# kludge.net
KiCad netlist of a schematic drawn in EAGLE
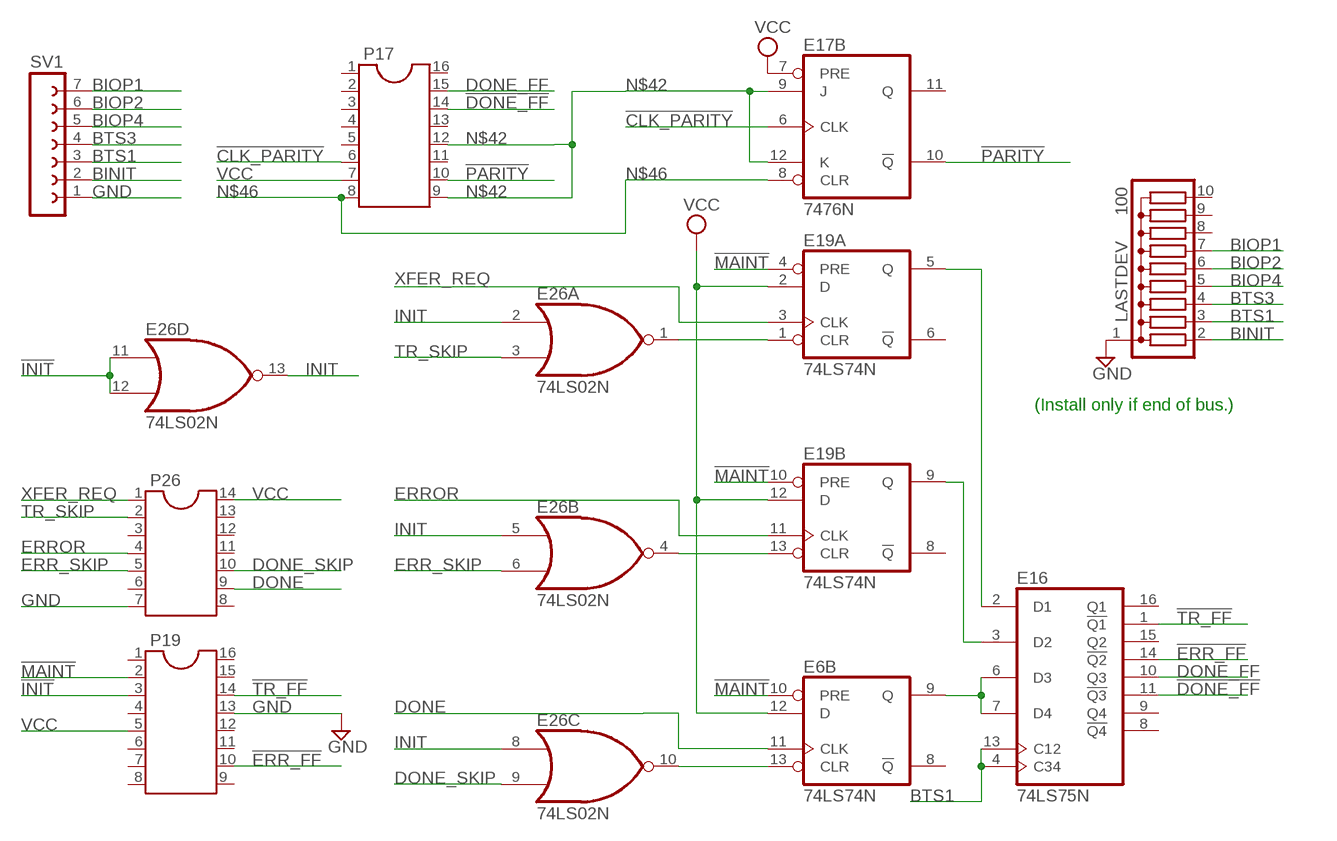
[diagram p0: schematic, sheet 1]

(export (version "E")
  (design (tool "Eeschema 10.0.6"))
  (components
    (comp (ref "E6")
      (value "74LS74N")
      (footprint "eagle-import:DIL14")
      (libsource (lib "eagle-import") (part "7474NLS"))
    )
    (comp (ref "E16")
      (value "74LS75N")
      (footprint "eagle-import:DIL16")
      (libsource (lib "eagle-import") (part "7475NLS"))
    )
    (comp (ref "E17")
      (value "7476N")
      (footprint "eagle-import:DIL16")
      (libsource (lib "eagle-import") (part "7476N"))
    )
    (comp (ref "E19")
      (value "74LS74N")
      (footprint "eagle-import:DIL14")
      (libsource (lib "eagle-import") (part "7474NLS"))
    )
    (comp (ref "E26")
      (value "74LS02N")
      (footprint "eagle-import:DIL14")
      (libsource (lib "eagle-import") (part "7402NLS"))
    )
    (comp (ref "LASTDEV")
      (value "100")
      (footprint "eagle-import:SIL10")
      (libsource (lib "eagle-import") (part "G09R"))
    )
    (comp (ref "P17")
      (value "DIL16")
      (footprint "eagle-import:DIL16")
      (libsource (lib "eagle-import") (part "DIL16"))
    )
    (comp (ref "P19")
      (value "DIL16")
      (footprint "eagle-import:DIL16")
      (libsource (lib "eagle-import") (part "DIL16"))
    )
    (comp (ref "P26")
      (value "DIL14")
      (footprint "eagle-import:DIL14")
      (libsource (lib "eagle-import") (part "DIL14"))
    )
    (comp (ref "SV1")
      (value "FE07-1")
      (footprint "eagle-import:FE07")
      (libsource (lib "eagle-import") (part "FE07-1"))
    )
  )
  (nets
    (net (code "1") (name "/BINIT") (class "Default")
      (node (ref "LASTDEV") (pin "2") (pinfunction "2_2") (pintype "passive"))
      (node (ref "SV1") (pin "2") (pinfunction "2_2") (pintype "passive"))
    )
    (net (code "2") (name "/BIOP1") (class "Default")
      (node (ref "LASTDEV") (pin "7") (pinfunction "7_7") (pintype "passive"))
      (node (ref "SV1") (pin "7") (pinfunction "7_7") (pintype "passive"))
    )
    (net (code "3") (name "/BIOP2") (class "Default")
      (node (ref "LASTDEV") (pin "6") (pinfunction "6_6") (pintype "passive"))
      (node (ref "SV1") (pin "6") (pinfunction "6_6") (pintype "passive"))
    )
    (net (code "4") (name "/BIOP4") (class "Default")
      (node (ref "LASTDEV") (pin "5") (pinfunction "5_5") (pintype "passive"))
      (node (ref "SV1") (pin "5") (pinfunction "5_5") (pintype "passive"))
    )
    (net (code "5") (name "/BTS1") (class "Default")
      (node (ref "E16") (pin "13") (pinfunction "C12_13") (pintype "input"))
      (node (ref "E16") (pin "4") (pinfunction "C34_4") (pintype "input"))
      (node (ref "LASTDEV") (pin "3") (pinfunction "3_3") (pintype "passive"))
      (node (ref "SV1") (pin "3") (pinfunction "3_3") (pintype "passive"))
    )
    (net (code "6") (name "/BTS3") (class "Default")
      (node (ref "LASTDEV") (pin "4") (pinfunction "4_4") (pintype "passive"))
      (node (ref "SV1") (pin "4") (pinfunction "4_4") (pintype "passive"))
    )
    (net (code "7") (name "/DONE") (class "Default")
      (node (ref "E6") (pin "11") (pinfunction "CLK_11") (pintype "input"))
      (node (ref "P26") (pin "9") (pinfunction "9_9") (pintype "passive"))
    )
    (net (code "8") (name "/DONE_FF") (class "Default")
      (node (ref "E16") (pin "10") (pinfunction "Q3_10") (pintype "output"))
      (node (ref "P17") (pin "15") (pinfunction "15_15") (pintype "passive"))
    )
    (net (code "9") (name "/DONE_SKIP") (class "Default")
      (node (ref "E26") (pin "9") (pinfunction "I1_9") (pintype "input"))
      (node (ref "P26") (pin "10") (pinfunction "10_10") (pintype "passive"))
    )
    (net (code "10") (name "/ERROR") (class "Default")
      (node (ref "E19") (pin "11") (pinfunction "CLK_11") (pintype "input"))
      (node (ref "P26") (pin "4") (pinfunction "4_4") (pintype "passive"))
    )
    (net (code "11") (name "/ERR_SKIP") (class "Default")
      (node (ref "E26") (pin "6") (pinfunction "I1_6") (pintype "input"))
      (node (ref "P26") (pin "5") (pinfunction "5_5") (pintype "passive"))
    )
    (net (code "12") (name "/INIT") (class "Default")
      (node (ref "E26") (pin "13") (pinfunction "O_13") (pintype "output"))
      (node (ref "E26") (pin "2") (pinfunction "I0_2") (pintype "input"))
      (node (ref "E26") (pin "5") (pinfunction "I0_5") (pintype "input"))
      (node (ref "E26") (pin "8") (pinfunction "I0_8") (pintype "input"))
    )
    (net (code "13") (name "/N$42") (class "Default")
      (node (ref "E17") (pin "12") (pinfunction "K_12") (pintype "input"))
      (node (ref "E17") (pin "9") (pinfunction "J_9") (pintype "input"))
      (node (ref "P17") (pin "12") (pinfunction "12_12") (pintype "passive"))
      (node (ref "P17") (pin "9") (pinfunction "9_9") (pintype "passive"))
    )
    (net (code "14") (name "/N$46") (class "Default")
      (node (ref "E17") (pin "8") (pinfunction "CLR_8") (pintype "input"))
      (node (ref "P17") (pin "8") (pinfunction "8_8") (pintype "passive"))
    )
    (net (code "15") (name "/TR_SKIP") (class "Default")
      (node (ref "E26") (pin "3") (pinfunction "I1_3") (pintype "input"))
      (node (ref "P26") (pin "2") (pinfunction "2_2") (pintype "passive"))
    )
    (net (code "16") (name "/XFER_REQ") (class "Default")
      (node (ref "E19") (pin "3") (pinfunction "CLK_3") (pintype "input"))
      (node (ref "P26") (pin "1") (pinfunction "1_1") (pintype "passive"))
    )
    (net (code "17") (name "/~{CLK_PARITY}") (class "Default")
      (node (ref "E17") (pin "6") (pinfunction "CLK_6") (pintype "input"))
      (node (ref "P17") (pin "6") (pinfunction "6_6") (pintype "passive"))
    )
    (net (code "18") (name "/~{DONE_FF}") (class "Default")
      (node (ref "E16") (pin "11") (pinfunction "~{Q3}_11") (pintype "output"))
      (node (ref "P17") (pin "14") (pinfunction "14_14") (pintype "passive"))
    )
    (net (code "19") (name "/~{ERR_FF}") (class "Default")
      (node (ref "E16") (pin "14") (pinfunction "~{Q2}_14") (pintype "output"))
      (node (ref "P19") (pin "10") (pinfunction "10_10") (pintype "passive"))
    )
    (net (code "20") (name "/~{INIT}") (class "Default")
      (node (ref "E26") (pin "11") (pinfunction "I0_11") (pintype "input"))
      (node (ref "E26") (pin "12") (pinfunction "I1_12") (pintype "input"))
      (node (ref "P19") (pin "3") (pinfunction "3_3") (pintype "passive"))
    )
    (net (code "21") (name "/~{MAINT}") (class "Default")
      (node (ref "E19") (pin "10") (pinfunction "PRE_10") (pintype "input"))
      (node (ref "E19") (pin "4") (pinfunction "PRE_4") (pintype "input"))
      (node (ref "E6") (pin "10") (pinfunction "PRE_10") (pintype "input"))
      (node (ref "P19") (pin "2") (pinfunction "2_2") (pintype "passive"))
    )
    (net (code "22") (name "/~{PARITY}") (class "Default")
      (node (ref "E17") (pin "10") (pinfunction "~{Q}_10") (pintype "output"))
      (node (ref "P17") (pin "10") (pinfunction "10_10") (pintype "passive"))
    )
    (net (code "23") (name "/~{TR_FF}") (class "Default")
      (node (ref "E16") (pin "1") (pinfunction "~{Q1}_1") (pintype "output"))
      (node (ref "P19") (pin "14") (pinfunction "14_14") (pintype "passive"))
    )
    (net (code "24") (name "GND") (class "Default")
      (node (ref "LASTDEV") (pin "1") (pinfunction "1_1") (pintype "passive"))
      (node (ref "P19") (pin "13") (pinfunction "13_13") (pintype "passive"))
      (node (ref "P26") (pin "7") (pinfunction "7_7") (pintype "passive"))
      (node (ref "SV1") (pin "1") (pinfunction "1_1") (pintype "passive"))
    )
    (net (code "25") (name "Net-(E16A-D1)") (class "Default")
      (node (ref "E16") (pin "2") (pinfunction "D1_2") (pintype "input"))
      (node (ref "E19") (pin "5") (pinfunction "Q_5") (pintype "output"))
    )
    (net (code "26") (name "Net-(E16A-D2)") (class "Default")
      (node (ref "E16") (pin "3") (pinfunction "D2_3") (pintype "input"))
      (node (ref "E19") (pin "9") (pinfunction "Q_9") (pintype "output"))
    )
    (net (code "27") (name "Net-(E16A-D3)") (class "Default")
      (node (ref "E16") (pin "6") (pinfunction "D3_6") (pintype "input"))
      (node (ref "E16") (pin "7") (pinfunction "D4_7") (pintype "input"))
      (node (ref "E6") (pin "9") (pinfunction "Q_9") (pintype "output"))
    )
    (net (code "28") (name "Net-(E19A-CLR)") (class "Default")
      (node (ref "E19") (pin "1") (pinfunction "CLR_1") (pintype "input"))
      (node (ref "E26") (pin "1") (pinfunction "O_1") (pintype "output"))
    )
    (net (code "29") (name "Net-(E19B-CLR)") (class "Default")
      (node (ref "E19") (pin "13") (pinfunction "CLR_13") (pintype "input"))
      (node (ref "E26") (pin "4") (pinfunction "O_4") (pintype "output"))
    )
    (net (code "30") (name "Net-(E26C-O)") (class "Default")
      (node (ref "E26") (pin "10") (pinfunction "O_10") (pintype "output"))
      (node (ref "E6") (pin "13") (pinfunction "CLR_13") (pintype "input"))
    )
    (net (code "31") (name "VCC") (class "Default")
      (node (ref "E17") (pin "7") (pinfunction "PRE_7") (pintype "input"))
      (node (ref "E19") (pin "12") (pinfunction "D_12") (pintype "input"))
      (node (ref "E19") (pin "2") (pinfunction "D_2") (pintype "input"))
      (node (ref "E6") (pin "12") (pinfunction "D_12") (pintype "input"))
      (node (ref "P17") (pin "7") (pinfunction "7_7") (pintype "passive"))
      (node (ref "P19") (pin "5") (pinfunction "5_5") (pintype "passive"))
      (node (ref "P26") (pin "14") (pinfunction "14_14") (pintype "passive"))
    )
    (net (code "32") (name "unconnected-(E6B-~{Q}-Pad8)") (class "Default")
      (node (ref "E6") (pin "8") (pinfunction "~{Q}_8") (pintype "output"))
    )
    (net (code "33") (name "unconnected-(E16A-Q1-Pad16)") (class "Default")
      (node (ref "E16") (pin "16") (pinfunction "Q1_16") (pintype "output"))
    )
    (net (code "34") (name "unconnected-(E16A-Q2-Pad15)") (class "Default")
      (node (ref "E16") (pin "15") (pinfunction "Q2_15") (pintype "output"))
    )
    (net (code "35") (name "unconnected-(E16A-Q4-Pad9)") (class "Default")
      (node (ref "E16") (pin "9") (pinfunction "Q4_9") (pintype "output"))
    )
    (net (code "36") (name "unconnected-(E16A-~{Q4}-Pad8)") (class "Default")
      (node (ref "E16") (pin "8") (pinfunction "~{Q4}_8") (pintype "output"))
    )
    (net (code "37") (name "unconnected-(E17B-Q-Pad11)") (class "Default")
      (node (ref "E17") (pin "11") (pinfunction "Q_11") (pintype "output"))
    )
    (net (code "38") (name "unconnected-(E19A-~{Q}-Pad6)") (class "Default")
      (node (ref "E19") (pin "6") (pinfunction "~{Q}_6") (pintype "output"))
    )
    (net (code "39") (name "unconnected-(E19B-~{Q}-Pad8)") (class "Default")
      (node (ref "E19") (pin "8") (pinfunction "~{Q}_8") (pintype "output"))
    )
    (net (code "40") (name "unconnected-(LASTDEV-Pad8)") (class "Default")
      (node (ref "LASTDEV") (pin "8") (pinfunction "8_8") (pintype "passive"))
    )
    (net (code "41") (name "unconnected-(LASTDEV-Pad9)") (class "Default")
      (node (ref "LASTDEV") (pin "9") (pinfunction "9_9") (pintype "passive"))
    )
    (net (code "42") (name "unconnected-(LASTDEV-Pad10)") (class "Default")
      (node (ref "LASTDEV") (pin "10") (pinfunction "10_10") (pintype "passive"))
    )
    (net (code "43") (name "unconnected-(P17-Pad1)") (class "Default")
      (node (ref "P17") (pin "1") (pinfunction "1_1") (pintype "passive"))
    )
    (net (code "44") (name "unconnected-(P17-Pad2)") (class "Default")
      (node (ref "P17") (pin "2") (pinfunction "2_2") (pintype "passive"))
    )
    (net (code "45") (name "unconnected-(P17-Pad3)") (class "Default")
      (node (ref "P17") (pin "3") (pinfunction "3_3") (pintype "passive"))
    )
    (net (code "46") (name "unconnected-(P17-Pad4)") (class "Default")
      (node (ref "P17") (pin "4") (pinfunction "4_4") (pintype "passive"))
    )
    (net (code "47") (name "unconnected-(P17-Pad5)") (class "Default")
      (node (ref "P17") (pin "5") (pinfunction "5_5") (pintype "passive"))
    )
    (net (code "48") (name "unconnected-(P17-Pad11)") (class "Default")
      (node (ref "P17") (pin "11") (pinfunction "11_11") (pintype "passive"))
    )
    (net (code "49") (name "unconnected-(P17-Pad13)") (class "Default")
      (node (ref "P17") (pin "13") (pinfunction "13_13") (pintype "passive"))
    )
    (net (code "50") (name "unconnected-(P17-Pad16)") (class "Default")
      (node (ref "P17") (pin "16") (pinfunction "16_16") (pintype "passive"))
    )
    (net (code "51") (name "unconnected-(P19-Pad1)") (class "Default")
      (node (ref "P19") (pin "1") (pinfunction "1_1") (pintype "passive"))
    )
    (net (code "52") (name "unconnected-(P19-Pad4)") (class "Default")
      (node (ref "P19") (pin "4") (pinfunction "4_4") (pintype "passive"))
    )
    (net (code "53") (name "unconnected-(P19-Pad6)") (class "Default")
      (node (ref "P19") (pin "6") (pinfunction "6_6") (pintype "passive"))
    )
    (net (code "54") (name "unconnected-(P19-Pad7)") (class "Default")
      (node (ref "P19") (pin "7") (pinfunction "7_7") (pintype "passive"))
    )
    (net (code "55") (name "unconnected-(P19-Pad8)") (class "Default")
      (node (ref "P19") (pin "8") (pinfunction "8_8") (pintype "passive"))
    )
    (net (code "56") (name "unconnected-(P19-Pad9)") (class "Default")
      (node (ref "P19") (pin "9") (pinfunction "9_9") (pintype "passive"))
    )
    (net (code "57") (name "unconnected-(P19-Pad11)") (class "Default")
      (node (ref "P19") (pin "11") (pinfunction "11_11") (pintype "passive"))
    )
    (net (code "58") (name "unconnected-(P19-Pad12)") (class "Default")
      (node (ref "P19") (pin "12") (pinfunction "12_12") (pintype "passive"))
    )
    (net (code "59") (name "unconnected-(P19-Pad15)") (class "Default")
      (node (ref "P19") (pin "15") (pinfunction "15_15") (pintype "passive"))
    )
    (net (code "60") (name "unconnected-(P19-Pad16)") (class "Default")
      (node (ref "P19") (pin "16") (pinfunction "16_16") (pintype "passive"))
    )
    (net (code "61") (name "unconnected-(P26-Pad3)") (class "Default")
      (node (ref "P26") (pin "3") (pinfunction "3_3") (pintype "passive"))
    )
    (net (code "62") (name "unconnected-(P26-Pad6)") (class "Default")
      (node (ref "P26") (pin "6") (pinfunction "6_6") (pintype "passive"))
    )
    (net (code "63") (name "unconnected-(P26-Pad8)") (class "Default")
      (node (ref "P26") (pin "8") (pinfunction "8_8") (pintype "passive"))
    )
    (net (code "64") (name "unconnected-(P26-Pad11)") (class "Default")
      (node (ref "P26") (pin "11") (pinfunction "11_11") (pintype "passive"))
    )
    (net (code "65") (name "unconnected-(P26-Pad12)") (class "Default")
      (node (ref "P26") (pin "12") (pinfunction "12_12") (pintype "passive"))
    )
    (net (code "66") (name "unconnected-(P26-Pad13)") (class "Default")
      (node (ref "P26") (pin "13") (pinfunction "13_13") (pintype "passive"))
    )
  )
)
